# Eprom.net
KiCad netlist of a schematic drawn in Altium Designer
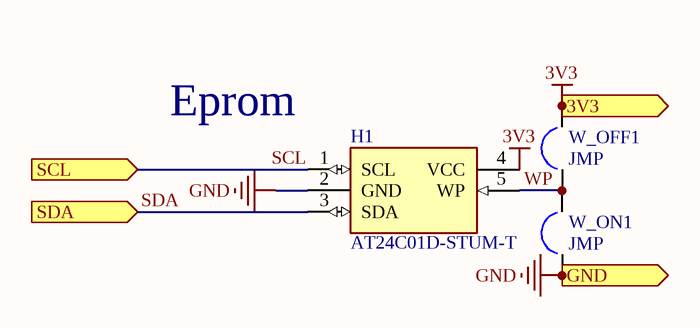
[diagram p0: Eprom.SchDoc]

(export (version "E")
  (design (tool "Eeschema 10.0.6"))
  (components
    (comp (ref "H1")
      (value "AT24C01D-STUM-T")
      (footprint "SOT95P280X145-5N")
      (description "Hardware")
      (fields
        (field (name "MOUSER PART NUMBER") "556-AT24C01D-STUM-T")
        (field (name "RS PART NUMBER") "8988614")
      )
      (libsource (lib "*") (part "AT24C01D-STUM-T"))
    )
    (comp (ref "W_OFF1") (value "JMP") (footprint "JMP") (libsource (lib "SamacSys") (part "JMP")))
    (comp (ref "W_ON1") (value "JMP") (footprint "JMP") (libsource (lib "SamacSys") (part "JMP")))
  )
  (nets
    (net (code "1") (name "/SCL") (class "Default")
      (node (ref "H1") (pin "1") (pinfunction "SCL_1") (pintype "bidirectional"))
    )
    (net (code "2") (name "/SDA") (class "Default")
      (node (ref "H1") (pin "3") (pinfunction "SDA_3") (pintype "bidirectional"))
    )
    (net (code "3") (name "/WP") (class "Default")
      (node (ref "H1") (pin "5") (pinfunction "WP_5") (pintype "input"))
      (node (ref "W_OFF1") (pin "1") (pinfunction "1_1") (pintype "passive"))
      (node (ref "W_ON1") (pin "2") (pinfunction "2_2") (pintype "passive"))
    )
    (net (code "4") (name "3V3") (class "Default")
      (node (ref "H1") (pin "4") (pinfunction "VCC_4") (pintype "power_in"))
      (node (ref "W_OFF1") (pin "2") (pinfunction "2_2") (pintype "passive"))
    )
    (net (code "5") (name "GND") (class "Default")
      (node (ref "H1") (pin "2") (pinfunction "GND_2") (pintype "power_in"))
      (node (ref "W_ON1") (pin "1") (pinfunction "1_1") (pintype "passive"))
    )
  )
)
